# Buffer_VCA.net
KiCad netlist of a schematic drawn in EAGLE
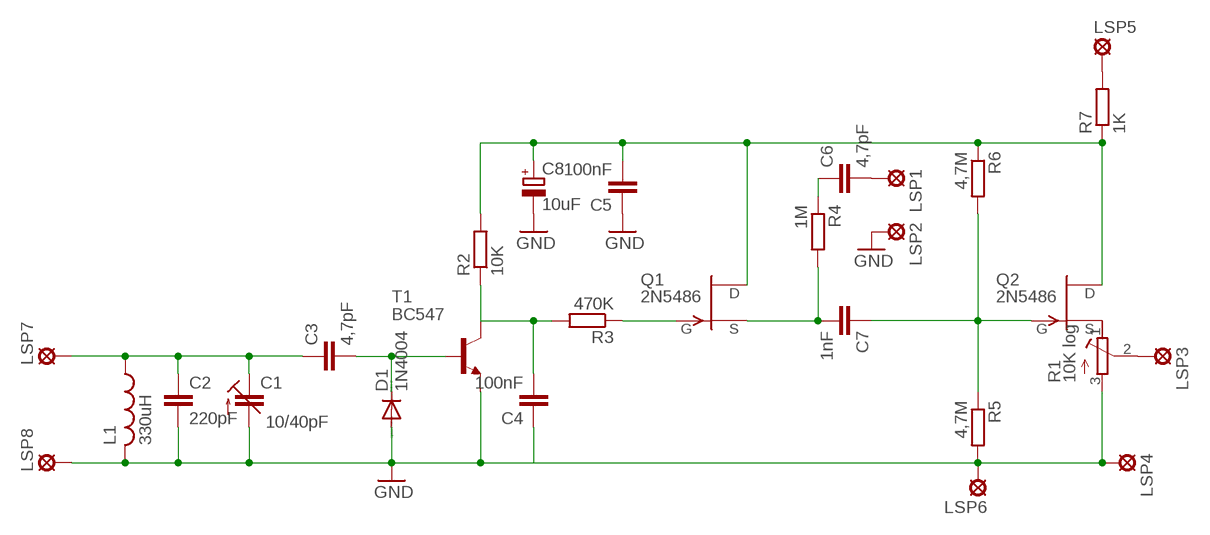
[diagram p0: schematic, sheet 1]

(export (version "E")
  (design (tool "Eeschema 10.0.6"))
  (components
    (comp (ref "C1")
      (value "10/40pF")
      (footprint "eagle-import:CTRIM808-BC")
      (libsource (lib "eagle-import") (part "C-TRIMM808"))
    )
    (comp (ref "C2")
      (value "220pF")
      (footprint "eagle-import:C050-024X044")
      (libsource (lib "eagle-import") (part "C-EU050-024X044"))
    )
    (comp (ref "C3")
      (value "4,7pF")
      (footprint "eagle-import:C050-024X044")
      (libsource (lib "eagle-import") (part "C-EU050-024X044"))
    )
    (comp (ref "C4")
      (value "100nF")
      (footprint "eagle-import:C050-024X044")
      (libsource (lib "eagle-import") (part "C-EU050-024X044"))
    )
    (comp (ref "C5")
      (value "100nF")
      (footprint "eagle-import:C050-024X044")
      (libsource (lib "eagle-import") (part "C-EU050-024X044"))
    )
    (comp (ref "C6")
      (value "4,7pF")
      (footprint "eagle-import:C050-024X044")
      (libsource (lib "eagle-import") (part "C-EU050-024X044"))
    )
    (comp (ref "C7")
      (value "1nF")
      (footprint "eagle-import:C050-024X044")
      (libsource (lib "eagle-import") (part "C-EU050-024X044"))
    )
    (comp (ref "C8")
      (value "10uF")
      (footprint "eagle-import:E3,5-10")
      (libsource (lib "eagle-import") (part "CPOL-EUE3.5-10"))
    )
    (comp (ref "D1")
      (value "1N4004")
      (footprint "eagle-import:DO41-10")
      (libsource (lib "eagle-import") (part "1N4004"))
    )
    (comp (ref "L1")
      (value "330uH")
      (footprint "eagle-import:0204_7")
      (libsource (lib "eagle-import") (part "L-US0204/7"))
    )
    (comp (ref "LSP1")
      (value "LSP10")
      (footprint "eagle-import:LSP10")
      (libsource (lib "eagle-import") (part "LSP10"))
    )
    (comp (ref "LSP2")
      (value "LSP10")
      (footprint "eagle-import:LSP10")
      (libsource (lib "eagle-import") (part "LSP10"))
    )
    (comp (ref "LSP3")
      (value "LSP10")
      (footprint "eagle-import:LSP10")
      (libsource (lib "eagle-import") (part "LSP10"))
    )
    (comp (ref "LSP4")
      (value "LSP10")
      (footprint "eagle-import:LSP10")
      (libsource (lib "eagle-import") (part "LSP10"))
    )
    (comp (ref "LSP5")
      (value "LSP10")
      (footprint "eagle-import:LSP10")
      (libsource (lib "eagle-import") (part "LSP10"))
    )
    (comp (ref "LSP6")
      (value "LSP10")
      (footprint "eagle-import:LSP10")
      (libsource (lib "eagle-import") (part "LSP10"))
    )
    (comp (ref "LSP7")
      (value "LSP10")
      (footprint "eagle-import:LSP10")
      (libsource (lib "eagle-import") (part "LSP10"))
    )
    (comp (ref "LSP8")
      (value "LSP10")
      (footprint "eagle-import:LSP10")
      (libsource (lib "eagle-import") (part "LSP10"))
    )
    (comp (ref "Q1")
      (value "2N5486")
      (footprint "eagle-import:TO92-")
      (libsource (lib "eagle-import") (part "?5482N6"))
    )
    (comp (ref "Q2")
      (value "2N5486")
      (footprint "eagle-import:TO92-")
      (libsource (lib "eagle-import") (part "?5482N6"))
    )
    (comp (ref "R1")
      (value "10K log")
      (footprint "eagle-import:RTRIMT93XB")
      (libsource (lib "eagle-import") (part "R-TRIMMT93XB"))
    )
    (comp (ref "R2")
      (value "10K")
      (footprint "eagle-import:0207_10")
      (libsource (lib "eagle-import") (part "R-EU_0207/10"))
    )
    (comp (ref "R3")
      (value "470K")
      (footprint "eagle-import:0207_10")
      (libsource (lib "eagle-import") (part "R-EU_0207/10"))
    )
    (comp (ref "R4")
      (value "1M")
      (footprint "eagle-import:0207_10")
      (libsource (lib "eagle-import") (part "R-EU_0207/10"))
    )
    (comp (ref "R5")
      (value "4,7M")
      (footprint "eagle-import:0207_10")
      (libsource (lib "eagle-import") (part "R-EU_0207/10"))
    )
    (comp (ref "R6")
      (value "4,7M")
      (footprint "eagle-import:0207_10")
      (libsource (lib "eagle-import") (part "R-EU_0207/10"))
    )
    (comp (ref "R7")
      (value "1K")
      (footprint "eagle-import:0207_10")
      (libsource (lib "eagle-import") (part "R-EU_0207/10"))
    )
    (comp (ref "T1")
      (value "BC547")
      (footprint "eagle-import:TO92")
      (libsource (lib "eagle-import") (part "BC547"))
    )
  )
  (nets
    (net (code "1") (name "GND") (class "Default")
      (node (ref "C1") (pin "2") (pinfunction "A_2") (pintype "passive"))
      (node (ref "C2") (pin "2") (pinfunction "2_2") (pintype "passive"))
      (node (ref "C4") (pin "1") (pinfunction "1_1") (pintype "passive"))
      (node (ref "C5") (pin "1") (pinfunction "1_1") (pintype "passive"))
      (node (ref "C8") (pin "-") (pinfunction "-_-") (pintype "passive"))
      (node (ref "D1") (pin "A") (pinfunction "A_A") (pintype "passive"))
      (node (ref "L1") (pin "2") (pinfunction "2_2") (pintype "passive"))
      (node (ref "LSP2") (pin "MP") (pinfunction "MP_MP") (pintype "passive"))
      (node (ref "LSP4") (pin "MP") (pinfunction "MP_MP") (pintype "passive"))
      (node (ref "LSP6") (pin "MP") (pinfunction "MP_MP") (pintype "passive"))
      (node (ref "LSP8") (pin "MP") (pinfunction "MP_MP") (pintype "passive"))
      (node (ref "R1") (pin "3") (pinfunction "A_3") (pintype "passive"))
      (node (ref "R5") (pin "2") (pinfunction "2_2") (pintype "passive"))
      (node (ref "T1") (pin "1") (pinfunction "E_1") (pintype "passive"))
    )
    (net (code "2") (name "Net-(C1-E)") (class "Default")
      (node (ref "C1") (pin "1") (pinfunction "E_1") (pintype "passive"))
      (node (ref "C2") (pin "1") (pinfunction "1_1") (pintype "passive"))
      (node (ref "C3") (pin "1") (pinfunction "1_1") (pintype "passive"))
      (node (ref "L1") (pin "1") (pinfunction "1_1") (pintype "passive"))
      (node (ref "LSP7") (pin "MP") (pinfunction "MP_MP") (pintype "passive"))
    )
    (net (code "3") (name "Net-(C6-Pad1)") (class "Default")
      (node (ref "C6") (pin "1") (pinfunction "1_1") (pintype "passive"))
      (node (ref "R4") (pin "1") (pinfunction "1_1") (pintype "passive"))
    )
    (net (code "4") (name "Net-(C6-Pad2)") (class "Default")
      (node (ref "C6") (pin "2") (pinfunction "2_2") (pintype "passive"))
      (node (ref "LSP1") (pin "MP") (pinfunction "MP_MP") (pintype "passive"))
    )
    (net (code "5") (name "Net-(LSP5-PadMP)") (class "Default")
      (node (ref "LSP5") (pin "MP") (pinfunction "MP_MP") (pintype "passive"))
      (node (ref "R7") (pin "2") (pinfunction "2_2") (pintype "passive"))
    )
    (net (code "6") (name "Net-(Q1-D)") (class "Default")
      (node (ref "C5") (pin "2") (pinfunction "2_2") (pintype "passive"))
      (node (ref "C8") (pin "+") (pinfunction "+_+") (pintype "passive"))
      (node (ref "Q1") (pin "3") (pinfunction "D_3") (pintype "passive"))
      (node (ref "Q2") (pin "3") (pinfunction "D_3") (pintype "passive"))
      (node (ref "R2") (pin "2") (pinfunction "2_2") (pintype "passive"))
      (node (ref "R6") (pin "1") (pinfunction "1_1") (pintype "passive"))
      (node (ref "R7") (pin "1") (pinfunction "1_1") (pintype "passive"))
    )
    (net (code "7") (name "Net-(Q1-G)") (class "Default")
      (node (ref "Q1") (pin "1") (pinfunction "G_1") (pintype "passive"))
      (node (ref "R3") (pin "1") (pinfunction "1_1") (pintype "passive"))
    )
    (net (code "8") (name "Net-(Q1-S)") (class "Default")
      (node (ref "C7") (pin "2") (pinfunction "2_2") (pintype "passive"))
      (node (ref "Q1") (pin "2") (pinfunction "S_2") (pintype "passive"))
      (node (ref "R4") (pin "2") (pinfunction "2_2") (pintype "passive"))
    )
    (net (code "9") (name "Net-(Q2-G)") (class "Default")
      (node (ref "C7") (pin "1") (pinfunction "1_1") (pintype "passive"))
      (node (ref "Q2") (pin "1") (pinfunction "G_1") (pintype "passive"))
      (node (ref "R5") (pin "1") (pinfunction "1_1") (pintype "passive"))
      (node (ref "R6") (pin "2") (pinfunction "2_2") (pintype "passive"))
    )
    (net (code "10") (name "Net-(Q2-S)") (class "Default")
      (node (ref "Q2") (pin "2") (pinfunction "S_2") (pintype "passive"))
      (node (ref "R1") (pin "1") (pinfunction "E_1") (pintype "passive"))
    )
    (net (code "11") (name "Net-(R1-S)") (class "Default")
      (node (ref "LSP3") (pin "MP") (pinfunction "MP_MP") (pintype "passive"))
      (node (ref "R1") (pin "2") (pinfunction "S_2") (pintype "passive"))
    )
    (net (code "12") (name "Net-(T1-B)") (class "Default")
      (node (ref "C3") (pin "2") (pinfunction "2_2") (pintype "passive"))
      (node (ref "D1") (pin "C") (pinfunction "C_C") (pintype "passive"))
      (node (ref "T1") (pin "2") (pinfunction "B_2") (pintype "passive"))
    )
    (net (code "13") (name "Net-(T1-C)") (class "Default")
      (node (ref "C4") (pin "2") (pinfunction "2_2") (pintype "passive"))
      (node (ref "R2") (pin "1") (pinfunction "1_1") (pintype "passive"))
      (node (ref "R3") (pin "2") (pinfunction "2_2") (pintype "passive"))
      (node (ref "T1") (pin "3") (pinfunction "C_3") (pintype "passive"))
    )
  )
)
